# DCDC_12V_Servo.net
KiCad netlist of a schematic drawn in Altium Designer
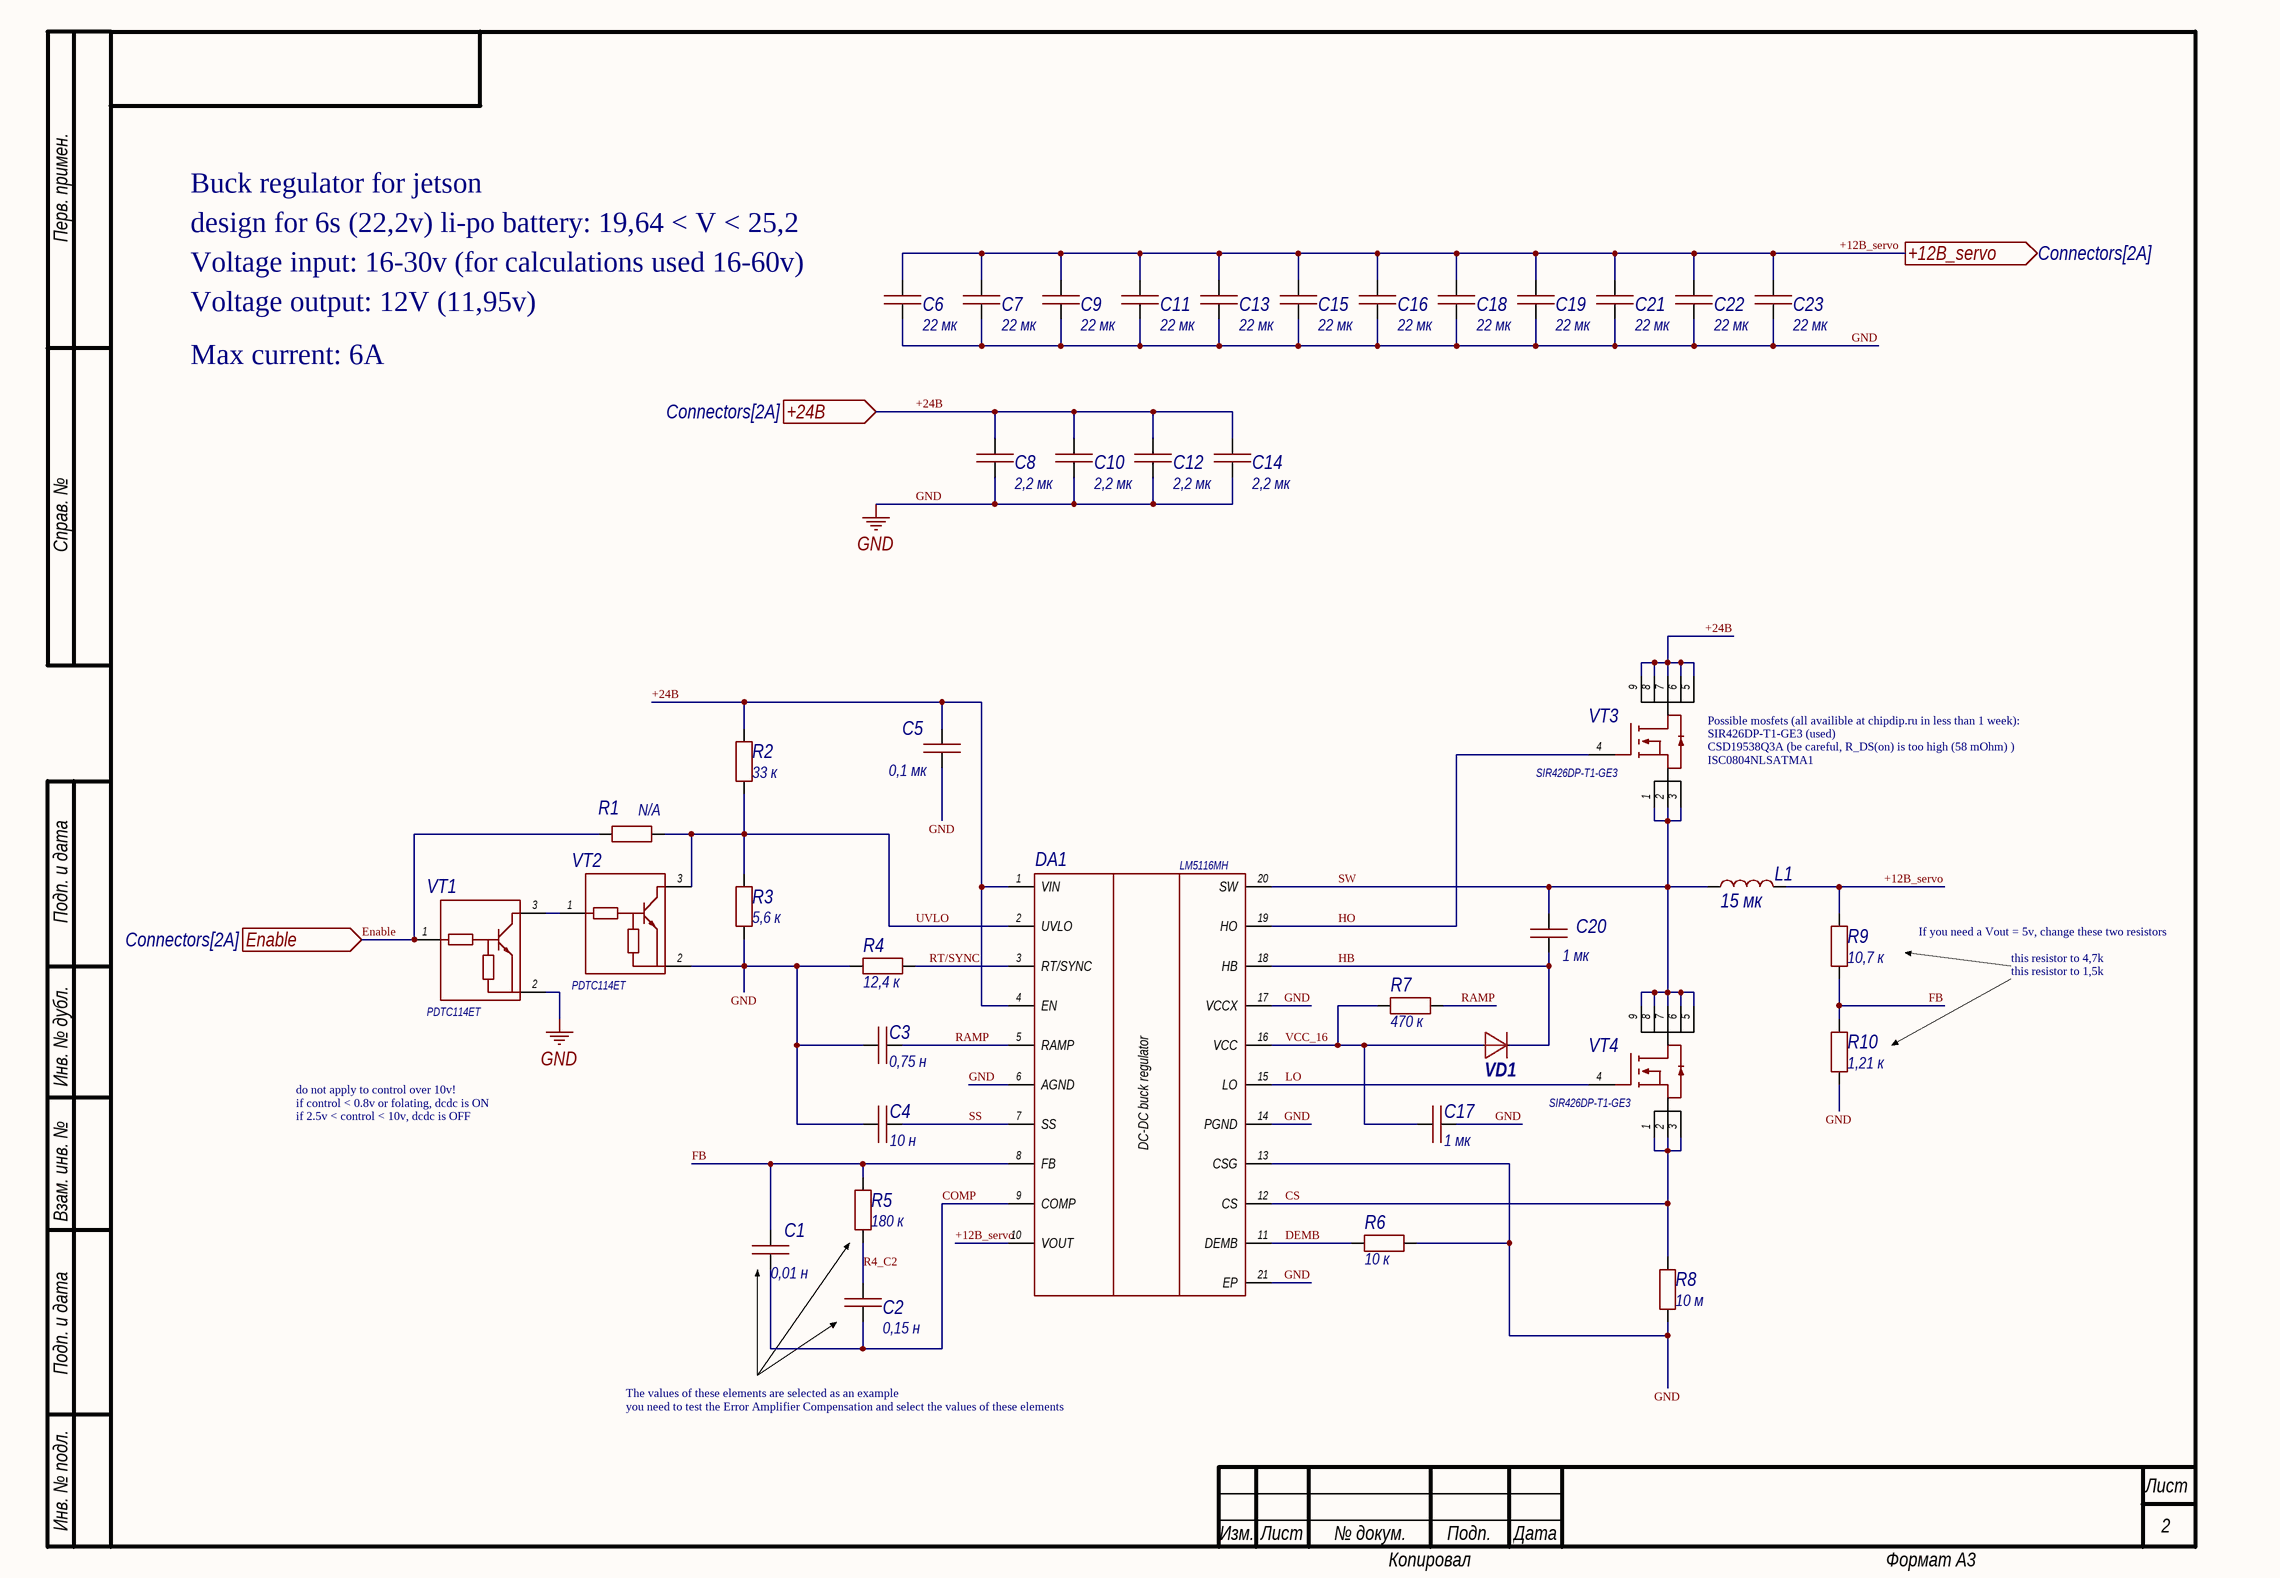
[diagram p0: DCDC_12V_Servo.SchDoc]

(export (version "E")
  (design (tool "Eeschema 10.0.6"))
  (components
    (comp (ref "C1")
      (value "0,01 н")
      (footprint "0603C")
      (description "Конденсатор")
      (fields
        (field (name "PART NUMBER") "Capacitor_0,01n_10_50V_X7R_0603C")
        (field (name "TOLERANCE") "0,1")
      )
      (libsource (lib "Hydrolib") (part "Capacitor"))
    )
    (comp (ref "C2")
      (value "0,15 н")
      (footprint "0603C")
      (description "Конденсатор")
      (fields
        (field (name "PART NUMBER") "Capacitor_0,15n_10_50V_X7R_0603C")
        (field (name "TOLERANCE") "0,1")
      )
      (libsource (lib "Hydrolib") (part "Capacitor"))
    )
    (comp (ref "C3")
      (value "0,75 н")
      (footprint "0603C")
      (description "Конденсатор")
      (fields
        (field (name "PART NUMBER") "Capacitor_0,75n_10_50V_X7R_0603C")
        (field (name "TOLERANCE") "0,1")
      )
      (libsource (lib "Hydrolib") (part "Capacitor"))
    )
    (comp (ref "C4")
      (value "10 н")
      (footprint "0603C")
      (description "Конденсатор")
      (fields (field (name "PART NUMBER") "Capacitor_10n_10_50V_X7R_0603C") (field (name "TOLERANCE") "0,1"))
      (libsource (lib "Hydrolib") (part "Capacitor"))
    )
    (comp (ref "C5")
      (value "0,1 мк")
      (footprint "0603C")
      (description "Конденсатор")
      (fields (field (name "PART NUMBER") "Capacitor_0,1u_10_50V_X7R_0603C") (field (name "TOLERANCE") "0,1"))
      (libsource (lib "Hydrolib") (part "Capacitor"))
    )
    (comp (ref "C6")
      (value "22 мк")
      (footprint "1210C")
      (description "Конденсатор")
      (fields (field (name "PART NUMBER") "Capacitor_22u_10_25V_X7R_1210C") (field (name "TOLERANCE") "0,1"))
      (libsource (lib "Hydrolib") (part "Capacitor"))
    )
    (comp (ref "C7")
      (value "22 мк")
      (footprint "1210C")
      (description "Конденсатор")
      (fields (field (name "PART NUMBER") "Capacitor_22u_10_25V_X7R_1210C") (field (name "TOLERANCE") "0,1"))
      (libsource (lib "Hydrolib") (part "Capacitor"))
    )
    (comp (ref "C8")
      (value "2,2 мк")
      (footprint "1206C")
      (description "Конденсатор")
      (fields (field (name "PART NUMBER") "Capacitor_2,2u_10_50V_X7R_1206C") (field (name "TOLERANCE") "0,1"))
      (libsource (lib "Hydrolib") (part "Capacitor"))
    )
    (comp (ref "C9")
      (value "22 мк")
      (footprint "1210C")
      (description "Конденсатор")
      (fields (field (name "PART NUMBER") "Capacitor_22u_10_25V_X7R_1210C") (field (name "TOLERANCE") "0,1"))
      (libsource (lib "Hydrolib") (part "Capacitor"))
    )
    (comp (ref "C10")
      (value "2,2 мк")
      (footprint "1206C")
      (description "Конденсатор")
      (fields (field (name "PART NUMBER") "Capacitor_2,2u_10_50V_X7R_1206C") (field (name "TOLERANCE") "0,1"))
      (libsource (lib "Hydrolib") (part "Capacitor"))
    )
    (comp (ref "C11")
      (value "22 мк")
      (footprint "1210C")
      (description "Конденсатор")
      (fields (field (name "PART NUMBER") "Capacitor_22u_10_25V_X7R_1210C") (field (name "TOLERANCE") "0,1"))
      (libsource (lib "Hydrolib") (part "Capacitor"))
    )
    (comp (ref "C12")
      (value "2,2 мк")
      (footprint "1206C")
      (description "Конденсатор")
      (fields (field (name "PART NUMBER") "Capacitor_2,2u_10_50V_X7R_1206C") (field (name "TOLERANCE") "0,1"))
      (libsource (lib "Hydrolib") (part "Capacitor"))
    )
    (comp (ref "C13")
      (value "22 мк")
      (footprint "1210C")
      (description "Конденсатор")
      (fields (field (name "PART NUMBER") "Capacitor_22u_10_25V_X7R_1210C") (field (name "TOLERANCE") "0,1"))
      (libsource (lib "Hydrolib") (part "Capacitor"))
    )
    (comp (ref "C14")
      (value "2,2 мк")
      (footprint "1206C")
      (description "Конденсатор")
      (fields (field (name "PART NUMBER") "Capacitor_2,2u_10_50V_X7R_1206C") (field (name "TOLERANCE") "0,1"))
      (libsource (lib "Hydrolib") (part "Capacitor"))
    )
    (comp (ref "C15")
      (value "22 мк")
      (footprint "1210C")
      (description "Конденсатор")
      (fields (field (name "PART NUMBER") "Capacitor_22u_10_25V_X7R_1210C") (field (name "TOLERANCE") "0,1"))
      (libsource (lib "Hydrolib") (part "Capacitor"))
    )
    (comp (ref "C16")
      (value "22 мк")
      (footprint "1210C")
      (description "Конденсатор")
      (fields (field (name "PART NUMBER") "Capacitor_22u_10_25V_X7R_1210C") (field (name "TOLERANCE") "0,1"))
      (libsource (lib "Hydrolib") (part "Capacitor"))
    )
    (comp (ref "C17")
      (value "1 мк")
      (footprint "0603C")
      (description "Конденсатор")
      (fields (field (name "PART NUMBER") "Capacitor_1u_10_50V_X7R_0603C") (field (name "TOLERANCE") "0,1"))
      (libsource (lib "Hydrolib") (part "Capacitor"))
    )
    (comp (ref "C18")
      (value "22 мк")
      (footprint "1210C")
      (description "Конденсатор")
      (fields (field (name "PART NUMBER") "Capacitor_22u_10_25V_X7R_1210C") (field (name "TOLERANCE") "0,1"))
      (libsource (lib "Hydrolib") (part "Capacitor"))
    )
    (comp (ref "C19")
      (value "22 мк")
      (footprint "1210C")
      (description "Конденсатор")
      (fields (field (name "PART NUMBER") "Capacitor_22u_10_25V_X7R_1210C") (field (name "TOLERANCE") "0,1"))
      (libsource (lib "Hydrolib") (part "Capacitor"))
    )
    (comp (ref "C20")
      (value "1 мк")
      (footprint "0603C")
      (description "Конденсатор")
      (fields (field (name "PART NUMBER") "Capacitor_1u_10_50V_X7R_0603C") (field (name "TOLERANCE") "0,1"))
      (libsource (lib "Hydrolib") (part "Capacitor"))
    )
    (comp (ref "C21")
      (value "22 мк")
      (footprint "1210C")
      (description "Конденсатор")
      (fields (field (name "PART NUMBER") "Capacitor_22u_10_25V_X7R_1210C") (field (name "TOLERANCE") "0,1"))
      (libsource (lib "Hydrolib") (part "Capacitor"))
    )
    (comp (ref "C22")
      (value "22 мк")
      (footprint "1210C")
      (description "Конденсатор")
      (fields (field (name "PART NUMBER") "Capacitor_22u_10_25V_X7R_1210C") (field (name "TOLERANCE") "0,1"))
      (libsource (lib "Hydrolib") (part "Capacitor"))
    )
    (comp (ref "C23")
      (value "22 мк")
      (footprint "1210C")
      (description "Конденсатор")
      (fields (field (name "PART NUMBER") "Capacitor_22u_10_25V_X7R_1210C") (field (name "TOLERANCE") "0,1"))
      (libsource (lib "Hydrolib") (part "Capacitor"))
    )
    (comp (ref "DA1")
      (value "LM5116MH")
      (footprint "HTSSOP-20")
      (description "dc-dc понижающий adj 6-100v")
      (fields (field (name "MANUFACTURER_PART_NUMBER") "LM5116MH/NOPB"))
      (libsource (lib "Hydrolib") (part "LM5116MH"))
    )
    (comp (ref "L1")
      (value "15 мк")
      (footprint "SPRH127")
      (description "Индуктивность на 15 мкГн, номинальный ток 8,4 А")
      (fields (field (name "PART NUMBER") "CDSPRH127-150M"))
      (libsource (lib "Hydrolib") (part "Inductance"))
    )
    (comp (ref "R1")
      (value "N/A")
      (footprint "0603R")
      (description "посадочное место 0603 под перемычку")
      (fields (field (name "PART NUMBER") "res_0603_N/A") (field (name "TOLERANCE") "1%"))
      (libsource (lib "") (part "Resistor_1"))
    )
    (comp (ref "R2")
      (value "33 к")
      (footprint "0603R")
      (description "Резистор номиналом 33 кОм и точностью 1%")
      (fields (field (name "PART NUMBER") "Resistor_33k_1_0603") (field (name "TOLERANCE") "1%"))
      (libsource (lib "Hydrolib") (part "Resistor"))
    )
    (comp (ref "R3")
      (value "5,6 к")
      (footprint "0603R")
      (description "Резистор номиналом 5,6 кОм 1%")
      (fields (field (name "PART NUMBER") "Resistor_5.6k_1_0603") (field (name "TOLERANCE") "1%"))
      (libsource (lib "Hydrolib") (part "Resistor"))
    )
    (comp (ref "R4")
      (value "12,4 к")
      (footprint "0603R")
      (description "Резистор номиналом 12,4 кОм и точностью 1%")
      (fields (field (name "PART NUMBER") "Resistor_12.4k_1_0603") (field (name "TOLERANCE") "1%"))
      (libsource (lib "") (part "Resistor_1"))
    )
    (comp (ref "R5")
      (value "180 к")
      (footprint "0603R")
      (description "Резистор номиналом 180 кОм и точностью 1%")
      (fields (field (name "PART NUMBER") "Resistor_180k_1_0603") (field (name "TOLERANCE") "1%"))
      (libsource (lib "Hydrolib") (part "Resistor"))
    )
    (comp (ref "R6")
      (value "10 к")
      (footprint "0603R")
      (description "Резистор номиналом 10 кОм и точностью 1%")
      (fields (field (name "PART NUMBER") "Resistor_10k_1_0603") (field (name "TOLERANCE") "1%"))
      (libsource (lib "") (part "Resistor_1"))
    )
    (comp (ref "R7")
      (value "470 к")
      (footprint "0603R")
      (description "Резистор номиналом 470 кОм и точностью 1%")
      (fields (field (name "PART NUMBER") "Resistor_470k_1_0603") (field (name "TOLERANCE") "1%"))
      (libsource (lib "") (part "Resistor_1"))
    )
    (comp (ref "R8")
      (value "10 м")
      (footprint "1210R")
      (description "Резистор номиналом 10 мОм, точностью 1%, 0.5Вт")
      (fields (field (name "PART NUMBER") "RL1210FR-070R01L") (field (name "TOLERANCE") "1%"))
      (libsource (lib "Hydrolib") (part "Resistor"))
    )
    (comp (ref "R9")
      (value "10,7 к")
      (footprint "0603R")
      (description "Резистор номиналом 10,7 кОм и точностью 1%")
      (fields (field (name "PART NUMBER") "Resistor_10.7k_1_0603") (field (name "TOLERANCE") "1%"))
      (libsource (lib "Hydrolib") (part "Resistor"))
    )
    (comp (ref "R10")
      (value "1,21 к")
      (footprint "0603R")
      (description "Резистор номиналом 1,21 кОм и точностью 1%")
      (fields (field (name "PART NUMBER") "Resistor_1.21k_1_0603") (field (name "TOLERANCE") "1%"))
      (libsource (lib "Hydrolib") (part "Resistor"))
    )
    (comp (ref "VD1")
      (value "ES1D-E3/61T")
      (footprint "SMA")
      (description "Диод 1A 200V")
      (libsource (lib "Hydrolib") (part "Rectifier_diode"))
    )
    (comp (ref "VT1")
      (value "PDTC114ET")
      (footprint "SOT23-3")
      (description "цифровой npn 50в 100мА")
      (libsource (lib "Hydrolib") (part "PDTC114ET"))
    )
    (comp (ref "VT2")
      (value "PDTC114ET")
      (footprint "SOT23-3")
      (description "цифровой npn 50в 100мА")
      (libsource (lib "Hydrolib") (part "PDTC114ET"))
    )
    (comp (ref "VT3")
      (value "SIR426DP-T1-GE3")
      (footprint "PowerPAK_SO-8")
      (description "Транзистор полевой MOSFET N-канальный 40В 41.7Вт")
      (libsource (lib "Hydrolib") (part "SIR426DP-T1-GE3"))
    )
    (comp (ref "VT4")
      (value "SIR426DP-T1-GE3")
      (footprint "PowerPAK_SO-8")
      (description "Транзистор полевой MOSFET N-канальный 40В 41.7Вт")
      (libsource (lib "Hydrolib") (part "SIR426DP-T1-GE3"))
    )
  )
  (nets
    (net (code "1") (name "/+12В_servo") (class "Default")
      (node (ref "C11") (pin "2") (pinfunction "2_2") (pintype "passive"))
      (node (ref "C13") (pin "2") (pinfunction "2_2") (pintype "passive"))
      (node (ref "C15") (pin "2") (pinfunction "2_2") (pintype "passive"))
      (node (ref "C16") (pin "2") (pinfunction "2_2") (pintype "passive"))
      (node (ref "C18") (pin "2") (pinfunction "2_2") (pintype "passive"))
      (node (ref "C19") (pin "2") (pinfunction "2_2") (pintype "passive"))
      (node (ref "C21") (pin "2") (pinfunction "2_2") (pintype "passive"))
      (node (ref "C22") (pin "2") (pinfunction "2_2") (pintype "passive"))
      (node (ref "C23") (pin "2") (pinfunction "2_2") (pintype "passive"))
      (node (ref "C6") (pin "2") (pinfunction "2_2") (pintype "passive"))
      (node (ref "C7") (pin "2") (pinfunction "2_2") (pintype "passive"))
      (node (ref "C9") (pin "2") (pinfunction "2_2") (pintype "passive"))
      (node (ref "DA1") (pin "10") (pinfunction "VOUT_10") (pintype "passive"))
      (node (ref "L1") (pin "2") (pinfunction "2_2") (pintype "passive"))
      (node (ref "R9") (pin "2") (pinfunction "2_2") (pintype "passive"))
    )
    (net (code "2") (name "/+24В") (class "Default")
      (node (ref "C10") (pin "2") (pinfunction "2_2") (pintype "passive"))
      (node (ref "C12") (pin "2") (pinfunction "2_2") (pintype "passive"))
      (node (ref "C14") (pin "2") (pinfunction "2_2") (pintype "passive"))
      (node (ref "C5") (pin "2") (pinfunction "2_2") (pintype "passive"))
      (node (ref "C8") (pin "2") (pinfunction "2_2") (pintype "passive"))
      (node (ref "DA1") (pin "1") (pinfunction "VIN_1") (pintype "passive"))
      (node (ref "DA1") (pin "4") (pinfunction "EN_4") (pintype "passive"))
      (node (ref "R2") (pin "2") (pinfunction "2_2") (pintype "passive"))
      (node (ref "VT3") (pin "5") (pinfunction "5_5") (pintype "passive"))
      (node (ref "VT3") (pin "6") (pinfunction "6_6") (pintype "passive"))
      (node (ref "VT3") (pin "7") (pinfunction "7_7") (pintype "passive"))
      (node (ref "VT3") (pin "8") (pinfunction "8_8") (pintype "passive"))
      (node (ref "VT3") (pin "9") (pinfunction "9_9") (pintype "passive"))
    )
    (net (code "3") (name "/COMP") (class "Default")
      (node (ref "C1") (pin "1") (pinfunction "1_1") (pintype "passive"))
      (node (ref "C2") (pin "1") (pinfunction "1_1") (pintype "passive"))
      (node (ref "DA1") (pin "9") (pinfunction "COMP_9") (pintype "passive"))
    )
    (net (code "4") (name "/CS") (class "Default")
      (node (ref "DA1") (pin "12") (pinfunction "CS_12") (pintype "passive"))
      (node (ref "R8") (pin "2") (pinfunction "2_2") (pintype "passive"))
      (node (ref "VT4") (pin "1") (pinfunction "1_1") (pintype "passive"))
      (node (ref "VT4") (pin "2") (pinfunction "2_2") (pintype "passive"))
      (node (ref "VT4") (pin "3") (pinfunction "3_3") (pintype "passive"))
    )
    (net (code "5") (name "/DEMB") (class "Default")
      (node (ref "DA1") (pin "11") (pinfunction "DEMB_11") (pintype "passive"))
      (node (ref "R6") (pin "1") (pinfunction "1_1") (pintype "passive"))
    )
    (net (code "6") (name "/Enable") (class "Default")
      (node (ref "R1") (pin "1") (pinfunction "1_1") (pintype "passive"))
      (node (ref "VT1") (pin "1") (pinfunction "B_1") (pintype "passive"))
    )
    (net (code "7") (name "/FB") (class "Default")
      (node (ref "C1") (pin "2") (pinfunction "2_2") (pintype "passive"))
      (node (ref "DA1") (pin "8") (pinfunction "FB_8") (pintype "passive"))
      (node (ref "R10") (pin "2") (pinfunction "2_2") (pintype "passive"))
      (node (ref "R5") (pin "2") (pinfunction "2_2") (pintype "passive"))
      (node (ref "R9") (pin "1") (pinfunction "1_1") (pintype "passive"))
    )
    (net (code "8") (name "/HB") (class "Default")
      (node (ref "C20") (pin "1") (pinfunction "1_1") (pintype "passive"))
      (node (ref "DA1") (pin "18") (pinfunction "HB_18") (pintype "passive"))
      (node (ref "VD1") (pin "2") (pinfunction "2_2") (pintype "passive"))
    )
    (net (code "9") (name "/HO") (class "Default")
      (node (ref "DA1") (pin "19") (pinfunction "HO_19") (pintype "passive"))
      (node (ref "VT3") (pin "4") (pinfunction "4_4") (pintype "passive"))
    )
    (net (code "10") (name "/LO") (class "Default")
      (node (ref "DA1") (pin "15") (pinfunction "LO_15") (pintype "passive"))
      (node (ref "VT4") (pin "4") (pinfunction "4_4") (pintype "passive"))
    )
    (net (code "11") (name "/R4_C2") (class "Default")
      (node (ref "C2") (pin "2") (pinfunction "2_2") (pintype "passive"))
      (node (ref "R5") (pin "1") (pinfunction "1_1") (pintype "passive"))
    )
    (net (code "12") (name "/RAMP") (class "Default")
      (node (ref "C3") (pin "2") (pinfunction "2_2") (pintype "passive"))
      (node (ref "DA1") (pin "5") (pinfunction "RAMP_5") (pintype "passive"))
      (node (ref "R7") (pin "2") (pinfunction "2_2") (pintype "passive"))
    )
    (net (code "13") (name "/RT{slash}SYNC") (class "Default")
      (node (ref "DA1") (pin "3") (pinfunction "RT/SYNC_3") (pintype "passive"))
      (node (ref "R4") (pin "2") (pinfunction "2_2") (pintype "passive"))
    )
    (net (code "14") (name "/SS") (class "Default")
      (node (ref "C4") (pin "2") (pinfunction "2_2") (pintype "passive"))
      (node (ref "DA1") (pin "7") (pinfunction "SS_7") (pintype "passive"))
    )
    (net (code "15") (name "/SW") (class "Default")
      (node (ref "C20") (pin "2") (pinfunction "2_2") (pintype "passive"))
      (node (ref "DA1") (pin "20") (pinfunction "SW_20") (pintype "passive"))
      (node (ref "L1") (pin "1") (pinfunction "1_1") (pintype "passive"))
      (node (ref "VT3") (pin "1") (pinfunction "1_1") (pintype "passive"))
      (node (ref "VT3") (pin "2") (pinfunction "2_2") (pintype "passive"))
      (node (ref "VT3") (pin "3") (pinfunction "3_3") (pintype "passive"))
      (node (ref "VT4") (pin "5") (pinfunction "5_5") (pintype "passive"))
      (node (ref "VT4") (pin "6") (pinfunction "6_6") (pintype "passive"))
      (node (ref "VT4") (pin "7") (pinfunction "7_7") (pintype "passive"))
      (node (ref "VT4") (pin "8") (pinfunction "8_8") (pintype "passive"))
      (node (ref "VT4") (pin "9") (pinfunction "9_9") (pintype "passive"))
    )
    (net (code "16") (name "/UVLO") (class "Default")
      (node (ref "DA1") (pin "2") (pinfunction "UVLO_2") (pintype "passive"))
      (node (ref "R1") (pin "2") (pinfunction "2_2") (pintype "passive"))
      (node (ref "R2") (pin "1") (pinfunction "1_1") (pintype "passive"))
      (node (ref "R3") (pin "2") (pinfunction "2_2") (pintype "passive"))
      (node (ref "VT2") (pin "3") (pinfunction "C_3") (pintype "passive"))
    )
    (net (code "17") (name "/VCC_16") (class "Default")
      (node (ref "C17") (pin "1") (pinfunction "1_1") (pintype "passive"))
      (node (ref "DA1") (pin "16") (pinfunction "VCC_16") (pintype "passive"))
      (node (ref "R7") (pin "1") (pinfunction "1_1") (pintype "passive"))
      (node (ref "VD1") (pin "1") (pinfunction "1_1") (pintype "passive"))
    )
    (net (code "18") (name "GND") (class "Default")
      (node (ref "C10") (pin "1") (pinfunction "1_1") (pintype "passive"))
      (node (ref "C11") (pin "1") (pinfunction "1_1") (pintype "passive"))
      (node (ref "C12") (pin "1") (pinfunction "1_1") (pintype "passive"))
      (node (ref "C13") (pin "1") (pinfunction "1_1") (pintype "passive"))
      (node (ref "C14") (pin "1") (pinfunction "1_1") (pintype "passive"))
      (node (ref "C15") (pin "1") (pinfunction "1_1") (pintype "passive"))
      (node (ref "C16") (pin "1") (pinfunction "1_1") (pintype "passive"))
      (node (ref "C17") (pin "2") (pinfunction "2_2") (pintype "passive"))
      (node (ref "C18") (pin "1") (pinfunction "1_1") (pintype "passive"))
      (node (ref "C19") (pin "1") (pinfunction "1_1") (pintype "passive"))
      (node (ref "C21") (pin "1") (pinfunction "1_1") (pintype "passive"))
      (node (ref "C22") (pin "1") (pinfunction "1_1") (pintype "passive"))
      (node (ref "C23") (pin "1") (pinfunction "1_1") (pintype "passive"))
      (node (ref "C3") (pin "1") (pinfunction "1_1") (pintype "passive"))
      (node (ref "C4") (pin "1") (pinfunction "1_1") (pintype "passive"))
      (node (ref "C5") (pin "1") (pinfunction "1_1") (pintype "passive"))
      (node (ref "C6") (pin "1") (pinfunction "1_1") (pintype "passive"))
      (node (ref "C7") (pin "1") (pinfunction "1_1") (pintype "passive"))
      (node (ref "C8") (pin "1") (pinfunction "1_1") (pintype "passive"))
      (node (ref "C9") (pin "1") (pinfunction "1_1") (pintype "passive"))
      (node (ref "DA1") (pin "13") (pinfunction "CSG_13") (pintype "passive"))
      (node (ref "DA1") (pin "14") (pinfunction "PGND_14") (pintype "passive"))
      (node (ref "DA1") (pin "17") (pinfunction "VCCX_17") (pintype "passive"))
      (node (ref "DA1") (pin "21") (pinfunction "EP_21") (pintype "passive"))
      (node (ref "DA1") (pin "6") (pinfunction "AGND_6") (pintype "passive"))
      (node (ref "R10") (pin "1") (pinfunction "1_1") (pintype "passive"))
      (node (ref "R3") (pin "1") (pinfunction "1_1") (pintype "passive"))
      (node (ref "R4") (pin "1") (pinfunction "1_1") (pintype "passive"))
      (node (ref "R6") (pin "2") (pinfunction "2_2") (pintype "passive"))
      (node (ref "R8") (pin "1") (pinfunction "1_1") (pintype "passive"))
      (node (ref "VT1") (pin "2") (pinfunction "E_2") (pintype "passive"))
      (node (ref "VT2") (pin "2") (pinfunction "E_2") (pintype "passive"))
    )
    (net (code "19") (name "Net-(VT1-C)") (class "Default")
      (node (ref "VT1") (pin "3") (pinfunction "C_3") (pintype "passive"))
      (node (ref "VT2") (pin "1") (pinfunction "B_1") (pintype "passive"))
    )
  )
)
